# Display.net
KiCad netlist of a schematic drawn in Altium Designer
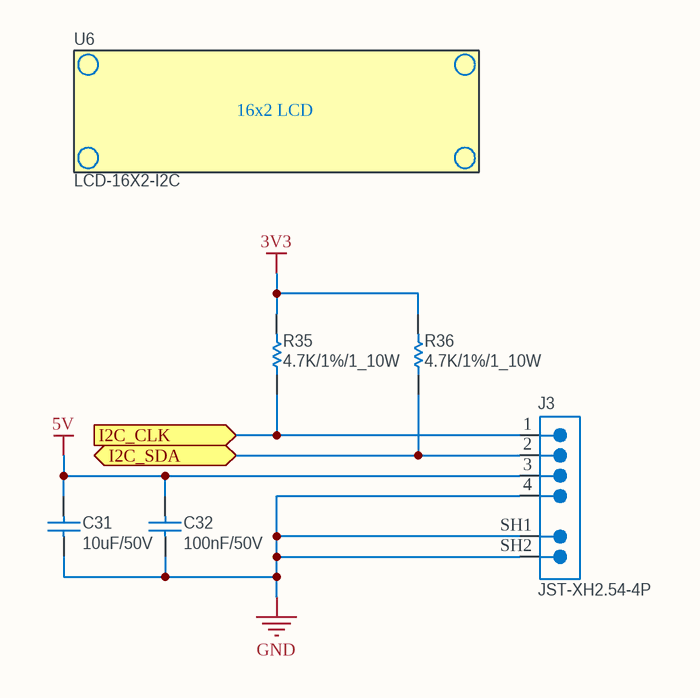
[diagram p0: Display.SchDoc]

(export (version "E")
  (design (tool "Eeschema 10.0.6"))
  (components
    (comp (ref "C31")
      (value "10uF/50V")
      (footprint "CAP_0805")
      (description "CAP, size 0805, 10uF, 50V")
      (fields (field (name "SUPPLY PART NUMBER") "Tụ Gốm 0805 10uF 50V"))
      (libsource (lib "BluetoothTracking") (part "Ceramic_Cap_10uF_50V_0805"))
    )
    (comp (ref "C32")
      (value "100nF/50V")
      (footprint "CAP_0805")
      (description "CAP, size 0805, 100nF, 50V")
      (fields (field (name "SUPPLY PART NUMBER") "Tụ Gốm 0805 100nF (0.1uF) 50V"))
      (libsource (lib "BluetoothTracking") (part "Ceramic_Cap_100nF_50V_0805"))
    )
    (comp (ref "J3")
      (value "JST-XH2.54-4P")
      (footprint "JST-XH2.54-4P")
      (description "XH2.54mm 4 Pin, SMD")
      (fields (field (name "SUPPLY PART NUMBER") "Đầu XH2.54mm 4 Chân Dán SMD Nằm Ngang"))
      (libsource (lib "BluetoothTracking") (part "JST-XH2.54-4P"))
    )
    (comp (ref "R35")
      (value "4.7K/1%/1_10W")
      (footprint "Resistor_0603")
      (description "Resistor 0603 4.7KOhm 1% 1_10W")
      (fields (field (name "SUPPLY PART NUMBER") "Điện Trở 4.7 KOhm 0603 1%"))
      (libsource (lib "BluetoothTracking") (part "Res_4.7K_0603_1%"))
    )
    (comp (ref "R36")
      (value "4.7K/1%/1_10W")
      (footprint "Resistor_0603")
      (description "Resistor 0603 4.7KOhm 1% 1_10W")
      (fields (field (name "SUPPLY PART NUMBER") "Điện Trở 4.7 KOhm 0603 1%"))
      (libsource (lib "BluetoothTracking") (part "Res_4.7K_0603_1%"))
    )
    (comp (ref "U6")
      (value "LCD-16X2-I2C")
      (footprint "MODULE_LCD-16X2")
      (description "Display Development Tools 16x2 Black on Green Char LCD w Backlight")
      (fields (field (name "SUPPLY PART NUMBER") "LCD 1602 Nền Xanh Lá Chữ Đen 5V Kèm I2C Driver"))
      (libsource (lib "BluetoothTracking") (part "LCD-16X2-I2C"))
    )
  )
  (nets
    (net (code "1") (name "/I2C_CLK") (class "Default")
      (node (ref "J3") (pin "1") (pinfunction "1_1") (pintype "passive"))
      (node (ref "R35") (pin "1") (pinfunction "1_1") (pintype "passive"))
    )
    (net (code "2") (name "/I2C_SDA") (class "Default")
      (node (ref "J3") (pin "2") (pinfunction "2_2") (pintype "passive"))
      (node (ref "R36") (pin "1") (pinfunction "1_1") (pintype "passive"))
    )
    (net (code "3") (name "3V3") (class "Default")
      (node (ref "R35") (pin "2") (pinfunction "2_2") (pintype "passive"))
      (node (ref "R36") (pin "2") (pinfunction "2_2") (pintype "passive"))
    )
    (net (code "4") (name "5V") (class "Default")
      (node (ref "C31") (pin "2") (pinfunction "2_2") (pintype "passive"))
      (node (ref "C32") (pin "2") (pinfunction "2_2") (pintype "passive"))
      (node (ref "J3") (pin "3") (pinfunction "3_3") (pintype "passive"))
    )
    (net (code "5") (name "GND") (class "Default")
      (node (ref "C31") (pin "1") (pinfunction "1_1") (pintype "passive"))
      (node (ref "C32") (pin "1") (pinfunction "1_1") (pintype "passive"))
      (node (ref "J3") (pin "4") (pinfunction "4_4") (pintype "passive"))
      (node (ref "J3") (pin "SH1") (pinfunction "SHIELD_SH1") (pintype "passive"))
      (node (ref "J3") (pin "SH2") (pinfunction "SHIELD_SH2") (pintype "passive"))
    )
  )
)
